# action_module_base.net
KiCad netlist of a schematic drawn in EAGLE
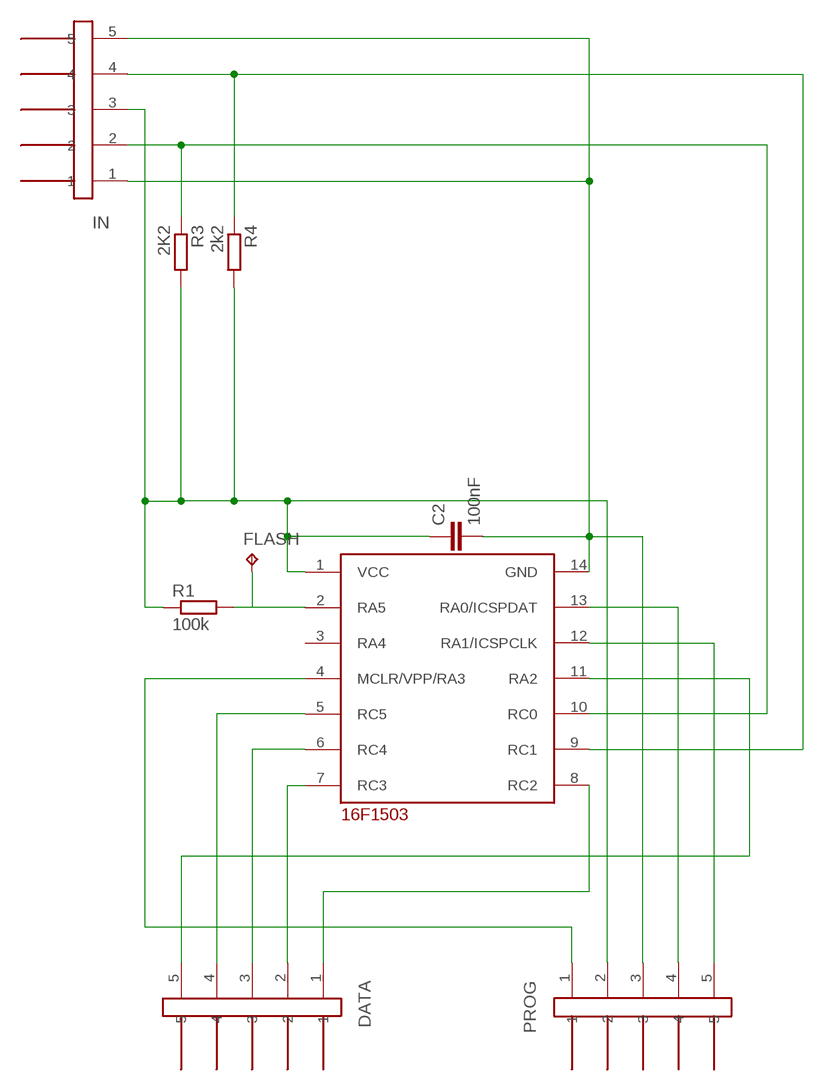
[diagram p0: schematic, sheet 1]

(export (version "E")
  (design (tool "Eeschema 10.0.6"))
  (components
    (comp (ref "C2")
      (value "100nF")
      (footprint "eagle-import:C0603K")
      (libsource (lib "eagle-import") (part "C-EUC0603K"))
    )
    (comp (ref "DATA")
      (value "JUMPER5M")
      (footprint "eagle-import:JUMPER5M")
      (libsource (lib "eagle-import") (part "JUMPER5M"))
    )
    (comp (ref "FLASH")
      (value "TPB1,27")
      (footprint "eagle-import:B1,27")
      (libsource (lib "eagle-import") (part "TPB1,27"))
    )
    (comp (ref "IN")
      (value "JUMPER5M-90")
      (footprint "eagle-import:JUMPER5M-90")
      (libsource (lib "eagle-import") (part "JUMPER5M-90"))
    )
    (comp (ref "PROG")
      (value "JUMPER5M")
      (footprint "eagle-import:JUMPER5M")
      (libsource (lib "eagle-import") (part "JUMPER5M"))
    )
    (comp (ref "R1")
      (value "100k")
      (footprint "eagle-import:R0603")
      (libsource (lib "eagle-import") (part "R-EU_R0603"))
    )
    (comp (ref "R3")
      (value "2K2")
      (footprint "eagle-import:R0603")
      (libsource (lib "eagle-import") (part "R-EU_R0603"))
    )
    (comp (ref "R4")
      (value "2k2")
      (footprint "eagle-import:R0603")
      (libsource (lib "eagle-import") (part "R-EU_R0603"))
    )
    (comp (ref "U1")
      (value "16F103-TSSOP")
      (footprint "eagle-import:TSSOP14")
      (libsource (lib "eagle-import") (part "16F103-TSSOP"))
    )
  )
  (nets
    (net (code "1") (name "Net-(U1-GND)") (class "Default")
      (node (ref "C2") (pin "2") (pinfunction "2_2") (pintype "passive"))
      (node (ref "IN") (pin "1") (pinfunction "1_1") (pintype "bidirectional"))
      (node (ref "IN") (pin "5") (pinfunction "5_5") (pintype "bidirectional"))
      (node (ref "PROG") (pin "3") (pinfunction "3_3") (pintype "bidirectional"))
      (node (ref "U1") (pin "14") (pinfunction "GND_14") (pintype "power_in"))
    )
    (net (code "2") (name "Net-(U1-MCLR{slash}VPP{slash}RA3)") (class "Default")
      (node (ref "PROG") (pin "1") (pinfunction "1_1") (pintype "bidirectional"))
      (node (ref "U1") (pin "4") (pinfunction "MCLR/VPP/RA3_4") (pintype "bidirectional"))
    )
    (net (code "3") (name "Net-(U1-RA0{slash}ICSPDAT)") (class "Default")
      (node (ref "PROG") (pin "4") (pinfunction "4_4") (pintype "bidirectional"))
      (node (ref "U1") (pin "13") (pinfunction "RA0/ICSPDAT_13") (pintype "bidirectional"))
    )
    (net (code "4") (name "Net-(U1-RA1{slash}ICSPCLK)") (class "Default")
      (node (ref "PROG") (pin "5") (pinfunction "5_5") (pintype "bidirectional"))
      (node (ref "U1") (pin "12") (pinfunction "RA1/ICSPCLK_12") (pintype "bidirectional"))
    )
    (net (code "5") (name "Net-(U1-RA2)") (class "Default")
      (node (ref "DATA") (pin "5") (pinfunction "5_5") (pintype "bidirectional"))
      (node (ref "U1") (pin "11") (pinfunction "RA2_11") (pintype "bidirectional"))
    )
    (net (code "6") (name "Net-(U1-RA5)") (class "Default")
      (node (ref "FLASH") (pin "TP") (pinfunction "TP_TP") (pintype "input"))
      (node (ref "R1") (pin "2") (pinfunction "2_2") (pintype "passive"))
      (node (ref "U1") (pin "2") (pinfunction "RA5_2") (pintype "bidirectional"))
    )
    (net (code "7") (name "Net-(U1-RC0)") (class "Default")
      (node (ref "IN") (pin "2") (pinfunction "2_2") (pintype "bidirectional"))
      (node (ref "R3") (pin "1") (pinfunction "1_1") (pintype "passive"))
      (node (ref "U1") (pin "10") (pinfunction "RC0_10") (pintype "bidirectional"))
    )
    (net (code "8") (name "Net-(U1-RC1)") (class "Default")
      (node (ref "IN") (pin "4") (pinfunction "4_4") (pintype "bidirectional"))
      (node (ref "R4") (pin "1") (pinfunction "1_1") (pintype "passive"))
      (node (ref "U1") (pin "9") (pinfunction "RC1_9") (pintype "bidirectional"))
    )
    (net (code "9") (name "Net-(U1-RC2)") (class "Default")
      (node (ref "DATA") (pin "1") (pinfunction "1_1") (pintype "bidirectional"))
      (node (ref "U1") (pin "8") (pinfunction "RC2_8") (pintype "bidirectional"))
    )
    (net (code "10") (name "Net-(U1-RC3)") (class "Default")
      (node (ref "DATA") (pin "2") (pinfunction "2_2") (pintype "bidirectional"))
      (node (ref "U1") (pin "7") (pinfunction "RC3_7") (pintype "bidirectional"))
    )
    (net (code "11") (name "Net-(U1-RC4)") (class "Default")
      (node (ref "DATA") (pin "3") (pinfunction "3_3") (pintype "bidirectional"))
      (node (ref "U1") (pin "6") (pinfunction "RC4_6") (pintype "bidirectional"))
    )
    (net (code "12") (name "Net-(U1-RC5)") (class "Default")
      (node (ref "DATA") (pin "4") (pinfunction "4_4") (pintype "bidirectional"))
      (node (ref "U1") (pin "5") (pinfunction "RC5_5") (pintype "bidirectional"))
    )
    (net (code "13") (name "Net-(U1-VCC)") (class "Default")
      (node (ref "C2") (pin "1") (pinfunction "1_1") (pintype "passive"))
      (node (ref "IN") (pin "3") (pinfunction "3_3") (pintype "bidirectional"))
      (node (ref "PROG") (pin "2") (pinfunction "2_2") (pintype "bidirectional"))
      (node (ref "R1") (pin "1") (pinfunction "1_1") (pintype "passive"))
      (node (ref "R3") (pin "2") (pinfunction "2_2") (pintype "passive"))
      (node (ref "R4") (pin "2") (pinfunction "2_2") (pintype "passive"))
      (node (ref "U1") (pin "1") (pinfunction "VCC_1") (pintype "power_in"))
    )
    (net (code "14") (name "unconnected-(U1-RA4-Pad3)") (class "Default")
      (node (ref "U1") (pin "3") (pinfunction "RA4_3") (pintype "bidirectional"))
    )
  )
)
